# E-18_Ultrasonic.net
KiCad netlist of a schematic drawn in Altium Designer
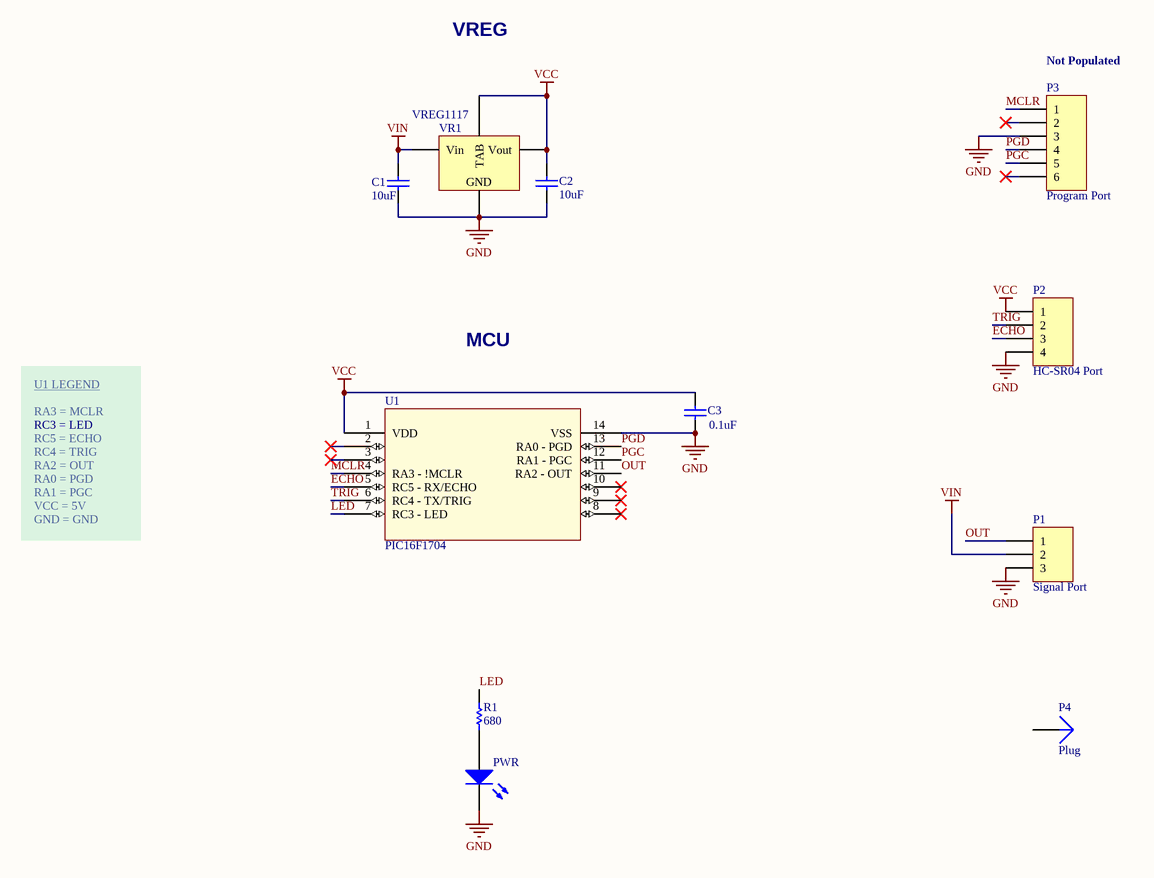
[diagram p0: E-18 Ultrasonic.SchDoc]

(export (version "E")
  (design (tool "Eeschema 10.0.6"))
  (components
    (comp (ref "C1")
      (value "10uF")
      (footprint "0805")
      (description "Capacitor")
      (fields (field (name "Comment") "Cap") (field (name "PUBLISHER") "Altium Limited"))
      (libsource (lib "SB_Discrete") (part "Cap"))
    )
    (comp (ref "C2")
      (value "10uF")
      (footprint "0805")
      (description "Capacitor")
      (fields (field (name "Comment") "Cap") (field (name "PUBLISHER") "Altium Limited"))
      (libsource (lib "SB_Discrete") (part "Cap"))
    )
    (comp (ref "C3")
      (value "0.1uF")
      (footprint "0805 TIGHT")
      (description "Capacitor")
      (fields (field (name "Comment") "18pF") (field (name "PUBLISHER") "Altium Limited"))
      (libsource (lib "SB_Discrete") (part "Cap"))
    )
    (comp (ref "P1")
      (value "Signal Port")
      (footprint "HDR1X3")
      (description "Header, 3-Pin")
      (fields (field (name "PUBLISHER") "Altium Limited"))
      (libsource (lib "Miscellaneous Connectors") (part "Header 3"))
    )
    (comp (ref "P2")
      (value "HC-SR04 Port")
      (footprint "HDR1X4")
      (description "Header, 4-Pin")
      (fields (field (name "PUBLISHER") "Altium Limited"))
      (libsource (lib "Miscellaneous Connectors") (part "Header 4"))
    )
    (comp (ref "P3")
      (value "Program Port")
      (footprint "HDR1X6")
      (description "Header, 6-Pin")
      (fields (field (name "PUBLISHER") "Altium Limited"))
      (libsource (lib "Miscellaneous Connectors") (part "Header 6"))
    )
    (comp (ref "P4")
      (value "Plug")
      (footprint "PIN1")
      (fields (field (name "PUBLISHER") "Altium Limited"))
      (libsource (lib "Miscellaneous Connectors") (part "Plug"))
    )
    (comp (ref "PWR")
      (value "LED1")
      (footprint "0805 LED - TIGHT")
      (description "Typical RED GaAs LED")
      (fields (field (name "PUBLISHER") "Altium Limited"))
      (libsource (lib "SB_Discrete") (part "LED1"))
    )
    (comp (ref "R1")
      (value "680")
      (footprint "0805 TIGHT")
      (description "Resistor")
      (fields (field (name "Comment") "Res1") (field (name "PUBLISHER") "Altium Limited"))
      (libsource (lib "SB_Discrete") (part "Res1"))
    )
    (comp (ref "U1")
      (value "PIC16F1704")
      (libsource (lib "SB_Engineered_Components") (part "PIC16F1704 - Ultrasonic"))
    )
    (comp (ref "VR1")
      (value "VREG1117")
      (footprint "VREG1117")
      (libsource (lib "SB_Engineered_Components") (part "VREG1117"))
    )
  )
  (nets
    (net (code "1") (name "/ECHO") (class "Default")
      (node (ref "P2") (pin "3") (pinfunction "3_3") (pintype "passive"))
      (node (ref "U1") (pin "5") (pinfunction "RC5_-_RX/ECHO_5") (pintype "bidirectional"))
    )
    (net (code "2") (name "/LED") (class "Default")
      (node (ref "R1") (pin "2") (pinfunction "2_2") (pintype "passive"))
      (node (ref "U1") (pin "7") (pinfunction "RC3_-_LED_7") (pintype "bidirectional"))
    )
    (net (code "3") (name "/MCLR") (class "Default")
      (node (ref "P3") (pin "1") (pinfunction "1_1") (pintype "passive"))
      (node (ref "U1") (pin "4") (pinfunction "RA3_-_!MCLR_4") (pintype "bidirectional"))
    )
    (net (code "4") (name "/OUT") (class "Default")
      (node (ref "P1") (pin "1") (pinfunction "1_1") (pintype "passive"))
      (node (ref "U1") (pin "11") (pinfunction "RA2_-_OUT_11") (pintype "bidirectional"))
    )
    (net (code "5") (name "/PGC") (class "Default")
      (node (ref "P3") (pin "5") (pinfunction "5_5") (pintype "passive"))
      (node (ref "U1") (pin "12") (pinfunction "RA1_-_PGC_12") (pintype "bidirectional"))
    )
    (net (code "6") (name "/PGD") (class "Default")
      (node (ref "P3") (pin "4") (pinfunction "4_4") (pintype "passive"))
      (node (ref "U1") (pin "13") (pinfunction "RA0_-_PGD_13") (pintype "bidirectional"))
    )
    (net (code "7") (name "/TRIG") (class "Default")
      (node (ref "P2") (pin "2") (pinfunction "2_2") (pintype "passive"))
      (node (ref "U1") (pin "6") (pinfunction "RC4_-_TX/TRIG_6") (pintype "bidirectional"))
    )
    (net (code "8") (name "GND") (class "Default")
      (node (ref "C1") (pin "2") (pinfunction "2_2") (pintype "passive"))
      (node (ref "C2") (pin "2") (pinfunction "2_2") (pintype "passive"))
      (node (ref "C3") (pin "1") (pinfunction "1_1") (pintype "passive"))
      (node (ref "P1") (pin "3") (pinfunction "3_3") (pintype "passive"))
      (node (ref "P2") (pin "4") (pinfunction "4_4") (pintype "passive"))
      (node (ref "P3") (pin "3") (pinfunction "3_3") (pintype "passive"))
      (node (ref "PWR") (pin "2") (pinfunction "K_2") (pintype "passive"))
      (node (ref "U1") (pin "14") (pinfunction "VSS_14") (pintype "power_in"))
      (node (ref "VR1") (pin "1") (pinfunction "GND_1") (pintype "passive"))
    )
    (net (code "9") (name "Net-(PWR-A)") (class "Default")
      (node (ref "PWR") (pin "1") (pinfunction "A_1") (pintype "passive"))
      (node (ref "R1") (pin "1") (pinfunction "1_1") (pintype "passive"))
    )
    (net (code "10") (name "VCC") (class "Default")
      (node (ref "C2") (pin "1") (pinfunction "1_1") (pintype "passive"))
      (node (ref "C3") (pin "2") (pinfunction "2_2") (pintype "passive"))
      (node (ref "P2") (pin "1") (pinfunction "1_1") (pintype "passive"))
      (node (ref "U1") (pin "1") (pinfunction "VDD_1") (pintype "power_in"))
      (node (ref "VR1") (pin "2") (pinfunction "TAB_2") (pintype "passive"))
    )
    (net (code "11") (name "VIN") (class "Default")
      (node (ref "C1") (pin "1") (pinfunction "1_1") (pintype "passive"))
      (node (ref "P1") (pin "2") (pinfunction "2_2") (pintype "passive"))
      (node (ref "VR1") (pin "3") (pinfunction "Vin_3") (pintype "passive"))
    )
    (net (code "12") (name "unconnected-(P3-Pad2)") (class "Default")
      (node (ref "P3") (pin "2") (pinfunction "2_2") (pintype "passive+no_connect"))
    )
    (net (code "13") (name "unconnected-(P3-Pad6)") (class "Default")
      (node (ref "P3") (pin "6") (pinfunction "6_6") (pintype "passive+no_connect"))
    )
    (net (code "14") (name "unconnected-(P4-Pad1)") (class "Default")
      (node (ref "P4") (pin "1") (pinfunction "1_1") (pintype "passive"))
    )
    (net (code "15") (name "unconnected-(U1-RA4-Pad3)") (class "Default")
      (node (ref "U1") (pin "3") (pinfunction "RA4_3") (pintype "bidirectional+no_connect"))
    )
    (net (code "16") (name "unconnected-(U1-RA5-Pad2)") (class "Default")
      (node (ref "U1") (pin "2") (pinfunction "RA5_2") (pintype "bidirectional+no_connect"))
    )
    (net (code "17") (name "unconnected-(U1-RC0-Pad10)") (class "Default")
      (node (ref "U1") (pin "10") (pinfunction "RC0_10") (pintype "bidirectional+no_connect"))
    )
    (net (code "18") (name "unconnected-(U1-RC1-Pad9)") (class "Default")
      (node (ref "U1") (pin "9") (pinfunction "RC1_9") (pintype "bidirectional+no_connect"))
    )
    (net (code "19") (name "unconnected-(U1-RC2-Pad8)") (class "Default")
      (node (ref "U1") (pin "8") (pinfunction "RC2_8") (pintype "bidirectional+no_connect"))
    )
  )
)
